# HeartRateSensor_Eval_Board_-_Si1141.net
KiCad netlist of a schematic drawn in EAGLE
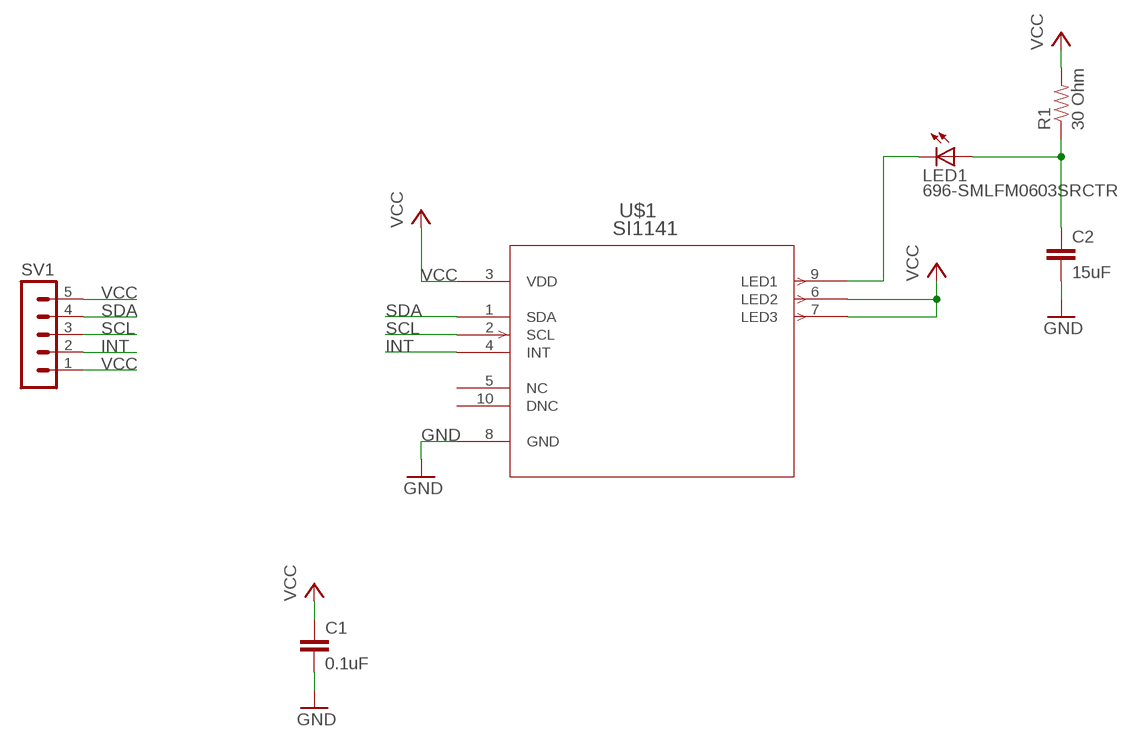
[diagram p0: schematic, sheet 1]

(export (version "E")
  (design (tool "Eeschema 10.0.6"))
  (components
    (comp (ref "C1")
      (value "0.1uF")
      (footprint "eagle-import:0603-CAP")
      (libsource (lib "eagle-import") (part "0.1UF-100V-10%(0603)"))
    )
    (comp (ref "C2")
      (value "15uF")
      (footprint "eagle-import:0603-CAP")
      (libsource (lib "eagle-import") (part "0.1UF-100V-10%(0603)"))
    )
    (comp (ref "LED1")
      (value "696-SMLFM0603SRCTR")
      (footprint "eagle-import:CHIP-LED0603")
      (libsource (lib "eagle-import") (part "LEDCHIP-LED0603"))
    )
    (comp (ref "R1")
      (value "30 Ohm")
      (footprint "eagle-import:0603")
      (libsource (lib "eagle-import") (part "0OHM1/10W5%(0603)"))
    )
    (comp (ref "SV1")
      (value "MA05-1")
      (footprint "eagle-import:MA05-1")
      (libsource (lib "eagle-import") (part "MA05-1"))
    )
    (comp (ref "U$1")
      (value "SI1141")
      (footprint "eagle-import:QFN10")
      (libsource (lib "eagle-import") (part "SI1141"))
    )
  )
  (nets
    (net (code "1") (name "/INT") (class "Default")
      (node (ref "SV1") (pin "2") (pinfunction "2_2") (pintype "passive"))
      (node (ref "U$1") (pin "4") (pinfunction "INT_4") (pintype "passive"))
    )
    (net (code "2") (name "/SCL") (class "Default")
      (node (ref "SV1") (pin "3") (pinfunction "3_3") (pintype "passive"))
      (node (ref "U$1") (pin "2") (pinfunction "SCL_2") (pintype "input"))
    )
    (net (code "3") (name "/SDA") (class "Default")
      (node (ref "SV1") (pin "4") (pinfunction "4_4") (pintype "passive"))
      (node (ref "U$1") (pin "1") (pinfunction "SDA_1") (pintype "passive"))
    )
    (net (code "4") (name "GND") (class "Default")
      (node (ref "C1") (pin "2") (pinfunction "2_2") (pintype "passive"))
      (node (ref "C2") (pin "2") (pinfunction "2_2") (pintype "passive"))
      (node (ref "U$1") (pin "8") (pinfunction "GND_8") (pintype "power_in"))
    )
    (net (code "5") (name "Net-(C2-Pad1)") (class "Default")
      (node (ref "C2") (pin "1") (pinfunction "1_1") (pintype "passive"))
      (node (ref "LED1") (pin "A") (pinfunction "A_A") (pintype "passive"))
      (node (ref "R1") (pin "1") (pinfunction "1_1") (pintype "passive"))
    )
    (net (code "6") (name "Net-(U$1-LED1)") (class "Default")
      (node (ref "LED1") (pin "C") (pinfunction "C_C") (pintype "passive"))
      (node (ref "U$1") (pin "9") (pinfunction "LED1_9") (pintype "output"))
    )
    (net (code "7") (name "VCC") (class "Default")
      (node (ref "C1") (pin "1") (pinfunction "1_1") (pintype "passive"))
      (node (ref "R1") (pin "2") (pinfunction "2_2") (pintype "passive"))
      (node (ref "SV1") (pin "1") (pinfunction "1_1") (pintype "passive"))
      (node (ref "SV1") (pin "5") (pinfunction "5_5") (pintype "passive"))
      (node (ref "U$1") (pin "3") (pinfunction "VDD_3") (pintype "power_in"))
      (node (ref "U$1") (pin "6") (pinfunction "LED2_6") (pintype "output"))
      (node (ref "U$1") (pin "7") (pinfunction "LED3_7") (pintype "output"))
    )
    (net (code "8") (name "unconnected-(U$1-DNC-Pad10)") (class "Default")
      (node (ref "U$1") (pin "10") (pinfunction "DNC_10") (pintype "no_connect"))
    )
    (net (code "9") (name "unconnected-(U$1-NC-Pad5)") (class "Default")
      (node (ref "U$1") (pin "5") (pinfunction "NC_5") (pintype "no_connect"))
    )
  )
)
